# psu.net
KiCad netlist of a schematic drawn in EAGLE
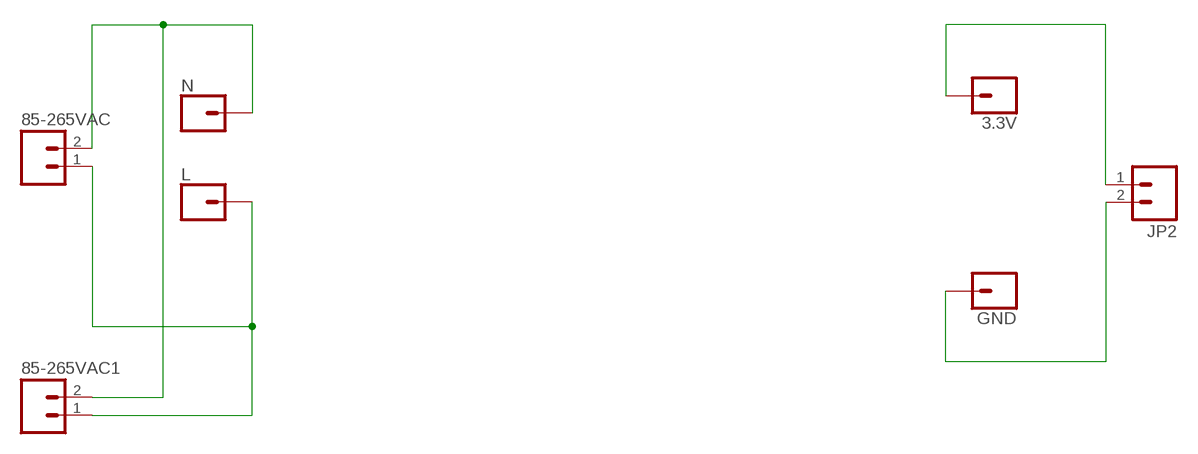
[diagram p0: schematic, sheet 1]

(export (version "E")
  (design (tool "Eeschema 10.0.6"))
  (components
    (comp (ref "3.3V")
      (value "CONN_01PTH_1.4MM")
      (footprint "eagle-import:1X01_1.4MM")
      (libsource (lib "eagle-import") (part "CONN_01PTH_1.4MM"))
    )
    (comp (ref "85-265VAC")
      (value "M02PTH3_5MM")
      (footprint "eagle-import:1X02_LONGPADS")
      (libsource (lib "eagle-import") (part "M02PTH3_5MM"))
    )
    (comp (ref "85-265VAC1")
      (value "M02PTH3_5MM")
      (footprint "eagle-import:1X02_LONGPADS")
      (libsource (lib "eagle-import") (part "M02PTH3_5MM"))
    )
    (comp (ref "GND")
      (value "CONN_01PTH_1.4MM")
      (footprint "eagle-import:1X01_1.4MM")
      (libsource (lib "eagle-import") (part "CONN_01PTH_1.4MM"))
    )
    (comp (ref "JP2")
      (value "M02PTH3_5MM")
      (footprint "eagle-import:1X02_LONGPADS")
      (libsource (lib "eagle-import") (part "M02PTH3_5MM"))
    )
    (comp (ref "L")
      (value "CONN_01PTH_1.4MM")
      (footprint "eagle-import:1X01_1.4MM")
      (libsource (lib "eagle-import") (part "CONN_01PTH_1.4MM"))
    )
    (comp (ref "N")
      (value "CONN_01PTH_1.4MM")
      (footprint "eagle-import:1X01_1.4MM")
      (libsource (lib "eagle-import") (part "CONN_01PTH_1.4MM"))
    )
  )
  (nets
    (net (code "1") (name "Net-(3.3V-Pad1)") (class "Default")
      (node (ref "3.3V") (pin "1") (pinfunction "1_1") (pintype "passive"))
      (node (ref "JP2") (pin "1") (pinfunction "1_1") (pintype "passive"))
    )
    (net (code "2") (name "Net-(85-265VAC-Pad1)") (class "Default")
      (node (ref "85-265VAC") (pin "1") (pinfunction "1_1") (pintype "passive"))
      (node (ref "85-265VAC1") (pin "1") (pinfunction "1_1") (pintype "passive"))
      (node (ref "L") (pin "1") (pinfunction "1_1") (pintype "passive"))
    )
    (net (code "3") (name "Net-(85-265VAC-Pad2)") (class "Default")
      (node (ref "85-265VAC") (pin "2") (pinfunction "2_2") (pintype "passive"))
      (node (ref "85-265VAC1") (pin "2") (pinfunction "2_2") (pintype "passive"))
      (node (ref "N") (pin "1") (pinfunction "1_1") (pintype "passive"))
    )
    (net (code "4") (name "Net-(GND-Pad1)") (class "Default")
      (node (ref "GND") (pin "1") (pinfunction "1_1") (pintype "passive"))
      (node (ref "JP2") (pin "2") (pinfunction "2_2") (pintype "passive"))
    )
  )
)
